# MinimusADC.net
KiCad netlist of a schematic drawn in EAGLE
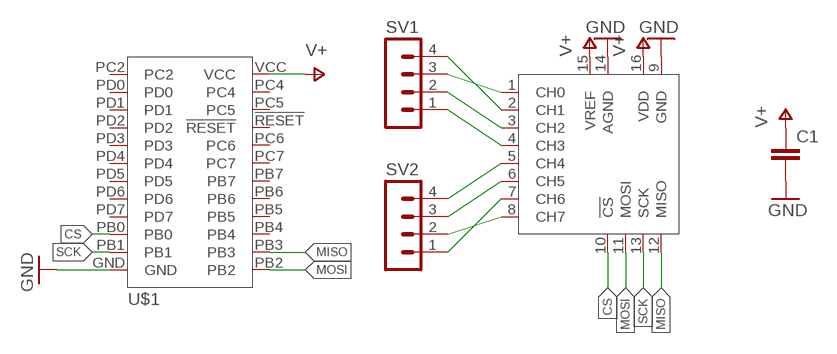
[diagram p0: schematic, sheet 1]

(export (version "E")
  (design (tool "Eeschema 10.0.6"))
  (components
    (comp (ref "C1")
      (value "C-EUC0805")
      (footprint "eagle-import:C0805")
      (libsource (lib "eagle-import") (part "C-EUC0805"))
    )
    (comp (ref "SV1")
      (value "MA04-1")
      (footprint "eagle-import:MA04-1")
      (libsource (lib "eagle-import") (part "MA04-1"))
    )
    (comp (ref "SV2")
      (value "MA04-1")
      (footprint "eagle-import:MA04-1")
      (libsource (lib "eagle-import") (part "MA04-1"))
    )
    (comp (ref "U$1")
      (value "MINIMUSNODIM")
      (footprint "eagle-import:MINIMUSNOPINS")
      (libsource (lib "eagle-import") (part "MINIMUSNODIM"))
    )
    (comp (ref "U$2")
      (value "MCP3008SL")
      (footprint "eagle-import:SO16")
      (libsource (lib "eagle-import") (part "MCP3008SL"))
    )
  )
  (nets
    (net (code "1") (name "CS") (class "Default")
      (node (ref "U$1") (pin "PB0") (pinfunction "PB0_PB0") (pintype "bidirectional"))
      (node (ref "U$2") (pin "10") (pinfunction "~{CS}_10") (pintype "input"))
    )
    (net (code "2") (name "GND") (class "Default")
      (node (ref "C1") (pin "2") (pinfunction "2_2") (pintype "passive"))
      (node (ref "U$1") (pin "GND") (pinfunction "GND_GND") (pintype "power_in"))
      (node (ref "U$2") (pin "14") (pinfunction "AGND_14") (pintype "power_in"))
      (node (ref "U$2") (pin "9") (pinfunction "GND_9") (pintype "power_in"))
    )
    (net (code "3") (name "MISO") (class "Default")
      (node (ref "U$1") (pin "PB3") (pinfunction "PB3_PB3") (pintype "bidirectional"))
      (node (ref "U$2") (pin "12") (pinfunction "MISO_12") (pintype "output"))
    )
    (net (code "4") (name "MOSI") (class "Default")
      (node (ref "U$1") (pin "PB2") (pinfunction "PB2_PB2") (pintype "bidirectional"))
      (node (ref "U$2") (pin "11") (pinfunction "MOSI_11") (pintype "input"))
    )
    (net (code "5") (name "Net-(U$2-CH0)") (class "Default")
      (node (ref "SV1") (pin "3") (pinfunction "3_3") (pintype "passive"))
      (node (ref "U$2") (pin "1") (pinfunction "CH0_1") (pintype "input"))
    )
    (net (code "6") (name "Net-(U$2-CH1)") (class "Default")
      (node (ref "SV1") (pin "4") (pinfunction "4_4") (pintype "passive"))
      (node (ref "U$2") (pin "2") (pinfunction "CH1_2") (pintype "input"))
    )
    (net (code "7") (name "Net-(U$2-CH2)") (class "Default")
      (node (ref "SV1") (pin "2") (pinfunction "2_2") (pintype "passive"))
      (node (ref "U$2") (pin "3") (pinfunction "CH2_3") (pintype "input"))
    )
    (net (code "8") (name "Net-(U$2-CH3)") (class "Default")
      (node (ref "SV1") (pin "1") (pinfunction "1_1") (pintype "passive"))
      (node (ref "U$2") (pin "4") (pinfunction "CH3_4") (pintype "input"))
    )
    (net (code "9") (name "Net-(U$2-CH4)") (class "Default")
      (node (ref "SV2") (pin "4") (pinfunction "4_4") (pintype "passive"))
      (node (ref "U$2") (pin "5") (pinfunction "CH4_5") (pintype "input"))
    )
    (net (code "10") (name "Net-(U$2-CH5)") (class "Default")
      (node (ref "SV2") (pin "3") (pinfunction "3_3") (pintype "passive"))
      (node (ref "U$2") (pin "6") (pinfunction "CH5_6") (pintype "input"))
    )
    (net (code "11") (name "Net-(U$2-CH6)") (class "Default")
      (node (ref "SV2") (pin "1") (pinfunction "1_1") (pintype "passive"))
      (node (ref "U$2") (pin "7") (pinfunction "CH6_7") (pintype "input"))
    )
    (net (code "12") (name "Net-(U$2-CH7)") (class "Default")
      (node (ref "SV2") (pin "2") (pinfunction "2_2") (pintype "passive"))
      (node (ref "U$2") (pin "8") (pinfunction "CH7_8") (pintype "input"))
    )
    (net (code "13") (name "SCK") (class "Default")
      (node (ref "U$1") (pin "PB1") (pinfunction "PB1_PB1") (pintype "bidirectional"))
      (node (ref "U$2") (pin "13") (pinfunction "SCK_13") (pintype "input"))
    )
    (net (code "14") (name "V+") (class "Default")
      (node (ref "C1") (pin "1") (pinfunction "1_1") (pintype "passive"))
      (node (ref "U$1") (pin "VCC") (pinfunction "VCC_VCC") (pintype "power_in"))
      (node (ref "U$2") (pin "15") (pinfunction "VREF_15") (pintype "power_in"))
      (node (ref "U$2") (pin "16") (pinfunction "VDD_16") (pintype "power_in"))
    )
    (net (code "15") (name "unconnected-(U$1-PadPB4)") (class "Default")
      (node (ref "U$1") (pin "PB4") (pinfunction "PB4_PB4") (pintype "bidirectional"))
    )
    (net (code "16") (name "unconnected-(U$1-PadPB5)") (class "Default")
      (node (ref "U$1") (pin "PB5") (pinfunction "PB5_PB5") (pintype "bidirectional"))
    )
    (net (code "17") (name "unconnected-(U$1-PadPB6)") (class "Default")
      (node (ref "U$1") (pin "PB6") (pinfunction "PB6_PB6") (pintype "bidirectional"))
    )
    (net (code "18") (name "unconnected-(U$1-PadPB7)") (class "Default")
      (node (ref "U$1") (pin "PB7") (pinfunction "PB7_PB7") (pintype "bidirectional"))
    )
    (net (code "19") (name "unconnected-(U$1-PadPC2)") (class "Default")
      (node (ref "U$1") (pin "PC2") (pinfunction "PC2_PC2") (pintype "bidirectional"))
    )
    (net (code "20") (name "unconnected-(U$1-PadPC4)") (class "Default")
      (node (ref "U$1") (pin "PC4") (pinfunction "PC4_PC4") (pintype "bidirectional"))
    )
    (net (code "21") (name "unconnected-(U$1-PadPC5)") (class "Default")
      (node (ref "U$1") (pin "PC5") (pinfunction "PC5_PC5") (pintype "bidirectional"))
    )
    (net (code "22") (name "unconnected-(U$1-PadPC6)") (class "Default")
      (node (ref "U$1") (pin "PC6") (pinfunction "PC6_PC6") (pintype "bidirectional"))
    )
    (net (code "23") (name "unconnected-(U$1-PadPC7)") (class "Default")
      (node (ref "U$1") (pin "PC7") (pinfunction "PC7_PC7") (pintype "bidirectional"))
    )
    (net (code "24") (name "unconnected-(U$1-PadPD0)") (class "Default")
      (node (ref "U$1") (pin "PD0") (pinfunction "PD0_PD0") (pintype "bidirectional"))
    )
    (net (code "25") (name "unconnected-(U$1-PadPD1)") (class "Default")
      (node (ref "U$1") (pin "PD1") (pinfunction "PD1_PD1") (pintype "bidirectional"))
    )
    (net (code "26") (name "unconnected-(U$1-PadPD2)") (class "Default")
      (node (ref "U$1") (pin "PD2") (pinfunction "PD2_PD2") (pintype "bidirectional"))
    )
    (net (code "27") (name "unconnected-(U$1-PadPD3)") (class "Default")
      (node (ref "U$1") (pin "PD3") (pinfunction "PD3_PD3") (pintype "bidirectional"))
    )
    (net (code "28") (name "unconnected-(U$1-PadPD4)") (class "Default")
      (node (ref "U$1") (pin "PD4") (pinfunction "PD4_PD4") (pintype "bidirectional"))
    )
    (net (code "29") (name "unconnected-(U$1-PadPD5)") (class "Default")
      (node (ref "U$1") (pin "PD5") (pinfunction "PD5_PD5") (pintype "bidirectional"))
    )
    (net (code "30") (name "unconnected-(U$1-PadPD6)") (class "Default")
      (node (ref "U$1") (pin "PD6") (pinfunction "PD6_PD6") (pintype "bidirectional"))
    )
    (net (code "31") (name "unconnected-(U$1-PadPD7)") (class "Default")
      (node (ref "U$1") (pin "PD7") (pinfunction "PD7_PD7") (pintype "bidirectional"))
    )
    (net (code "32") (name "unconnected-(U$1-~{RESET}-Pad!RESET)") (class "Default")
      (node (ref "U$1") (pin "!RESET") (pinfunction "~{RESET}_!RESET") (pintype "input"))
    )
  )
)
